# bme280_ssd1306.net
KiCad netlist of a schematic drawn in EAGLE
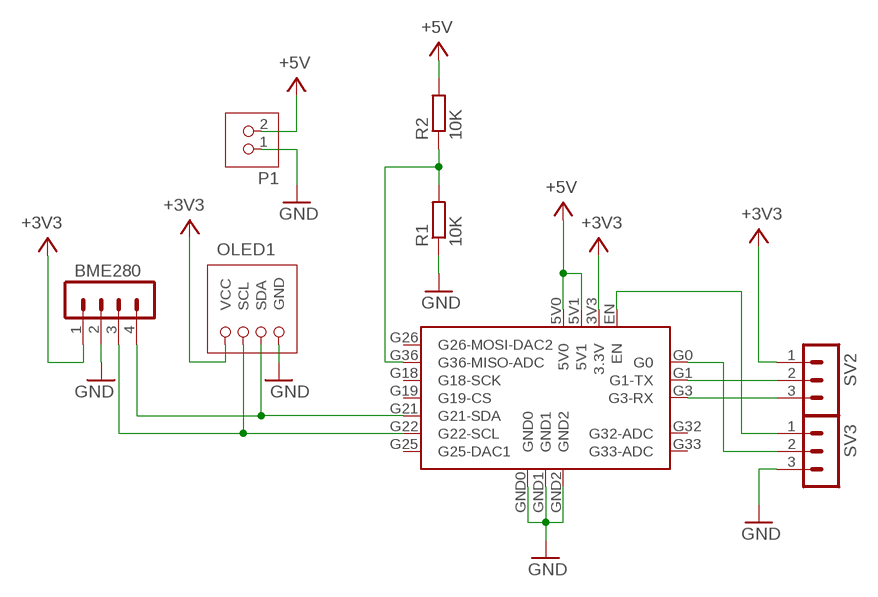
[diagram p0: schematic, sheet 1]

(export (version "E")
  (design (tool "Eeschema 10.0.6"))
  (components
    (comp (ref "BME280")
      (value "PINHEAD-MA04-1")
      (footprint "eagle-import:PINHEAD-MA04-1")
      (libsource (lib "eagle-import") (part "PINHEAD-MA04-1"))
    )
    (comp (ref "M5PICO1")
      (value "M5STAMP-PICO-SMD")
      (footprint "eagle-import:M5STAMP-PICO-SMD")
      (libsource (lib "eagle-import") (part "M5STAMP-PICO-SMD"))
    )
    (comp (ref "OLED1")
      (value "OLED-SSD1306-0.96")
      (footprint "eagle-import:OLED-I2C-0.96")
      (libsource (lib "eagle-import") (part "OLED-SSD1306-0.96"))
    )
    (comp (ref "P1")
      (value "JST-PH2")
      (footprint "eagle-import:JST-PH2")
      (libsource (lib "eagle-import") (part "JST-PH2"))
    )
    (comp (ref "R1")
      (value "10K")
      (footprint "eagle-import:R3216")
      (libsource (lib "eagle-import") (part "R-EU_R3216"))
    )
    (comp (ref "R2")
      (value "10K")
      (footprint "eagle-import:R3216")
      (libsource (lib "eagle-import") (part "R-EU_R3216"))
    )
    (comp (ref "SV2")
      (value "PINHEAD-MA03-1")
      (footprint "eagle-import:PINHEAD-MA03-1")
      (libsource (lib "eagle-import") (part "PINHEAD-MA03-1"))
    )
    (comp (ref "SV3")
      (value "PINHEAD-MA03-1")
      (footprint "eagle-import:PINHEAD-MA03-1")
      (libsource (lib "eagle-import") (part "PINHEAD-MA03-1"))
    )
  )
  (nets
    (net (code "1") (name "+3V3") (class "Default")
      (node (ref "BME280") (pin "1") (pinfunction "1_1") (pintype "passive"))
      (node (ref "M5PICO1") (pin "3V3") (pinfunction "3.3V_3V3") (pintype "bidirectional"))
      (node (ref "OLED1") (pin "VCC") (pinfunction "VCC_VCC") (pintype "bidirectional"))
      (node (ref "SV2") (pin "1") (pinfunction "1_1") (pintype "passive"))
    )
    (net (code "2") (name "+5V") (class "Default")
      (node (ref "M5PICO1") (pin "5V0") (pinfunction "5V0_5V0") (pintype "bidirectional"))
      (node (ref "M5PICO1") (pin "5V1") (pinfunction "5V1_5V1") (pintype "bidirectional"))
      (node (ref "P1") (pin "2") (pinfunction "2_2") (pintype "passive"))
      (node (ref "R2") (pin "2") (pinfunction "2_2") (pintype "passive"))
    )
    (net (code "3") (name "GND") (class "Default")
      (node (ref "BME280") (pin "2") (pinfunction "2_2") (pintype "passive"))
      (node (ref "M5PICO1") (pin "GND0") (pinfunction "GND0_GND0") (pintype "bidirectional"))
      (node (ref "M5PICO1") (pin "GND1") (pinfunction "GND1_GND1") (pintype "bidirectional"))
      (node (ref "M5PICO1") (pin "GND2") (pinfunction "GND2_GND2") (pintype "bidirectional"))
      (node (ref "OLED1") (pin "GND") (pinfunction "GND_GND") (pintype "bidirectional"))
      (node (ref "P1") (pin "1") (pinfunction "1_1") (pintype "passive"))
      (node (ref "R1") (pin "1") (pinfunction "1_1") (pintype "passive"))
      (node (ref "SV3") (pin "3") (pinfunction "3_3") (pintype "passive"))
    )
    (net (code "4") (name "Net-(M5PICO1-G1-TX)") (class "Default")
      (node (ref "M5PICO1") (pin "G1") (pinfunction "G1-TX_G1") (pintype "bidirectional"))
      (node (ref "SV2") (pin "2") (pinfunction "2_2") (pintype "passive"))
    )
    (net (code "5") (name "Net-(M5PICO1-G3-RX)") (class "Default")
      (node (ref "M5PICO1") (pin "G3") (pinfunction "G3-RX_G3") (pintype "bidirectional"))
      (node (ref "SV2") (pin "3") (pinfunction "3_3") (pintype "passive"))
    )
    (net (code "6") (name "Net-(M5PICO1-G21-SDA)") (class "Default")
      (node (ref "BME280") (pin "4") (pinfunction "4_4") (pintype "passive"))
      (node (ref "M5PICO1") (pin "G21") (pinfunction "G21-SDA_G21") (pintype "bidirectional"))
      (node (ref "OLED1") (pin "SDA") (pinfunction "SDA_SDA") (pintype "bidirectional"))
    )
    (net (code "7") (name "Net-(M5PICO1-G22-SCL)") (class "Default")
      (node (ref "BME280") (pin "3") (pinfunction "3_3") (pintype "passive"))
      (node (ref "M5PICO1") (pin "G22") (pinfunction "G22-SCL_G22") (pintype "bidirectional"))
      (node (ref "OLED1") (pin "SCL") (pinfunction "SCL_SCL") (pintype "bidirectional"))
    )
    (net (code "8") (name "Net-(M5PICO1-G36-MISO-ADC)") (class "Default")
      (node (ref "M5PICO1") (pin "G36") (pinfunction "G36-MISO-ADC_G36") (pintype "bidirectional"))
      (node (ref "R1") (pin "2") (pinfunction "2_2") (pintype "passive"))
      (node (ref "R2") (pin "1") (pinfunction "1_1") (pintype "passive"))
    )
    (net (code "9") (name "Net-(M5PICO1-PadEN)") (class "Default")
      (node (ref "M5PICO1") (pin "EN") (pinfunction "EN_EN") (pintype "bidirectional"))
      (node (ref "SV3") (pin "1") (pinfunction "1_1") (pintype "passive"))
    )
    (net (code "10") (name "Net-(M5PICO1-PadG0)") (class "Default")
      (node (ref "M5PICO1") (pin "G0") (pinfunction "G0_G0") (pintype "bidirectional"))
      (node (ref "SV3") (pin "2") (pinfunction "2_2") (pintype "passive"))
    )
    (net (code "11") (name "unconnected-(M5PICO1-G18-SCK-PadG18)") (class "Default")
      (node (ref "M5PICO1") (pin "G18") (pinfunction "G18-SCK_G18") (pintype "bidirectional"))
    )
    (net (code "12") (name "unconnected-(M5PICO1-G19-CS-PadG19)") (class "Default")
      (node (ref "M5PICO1") (pin "G19") (pinfunction "G19-CS_G19") (pintype "bidirectional"))
    )
    (net (code "13") (name "unconnected-(M5PICO1-G25-DAC1-PadG25)") (class "Default")
      (node (ref "M5PICO1") (pin "G25") (pinfunction "G25-DAC1_G25") (pintype "bidirectional"))
    )
    (net (code "14") (name "unconnected-(M5PICO1-G26-MOSI-DAC2-PadG26)") (class "Default")
      (node (ref "M5PICO1") (pin "G26") (pinfunction "G26-MOSI-DAC2_G26") (pintype "bidirectional"))
    )
    (net (code "15") (name "unconnected-(M5PICO1-G32-ADC-PadG32)") (class "Default")
      (node (ref "M5PICO1") (pin "G32") (pinfunction "G32-ADC_G32") (pintype "bidirectional"))
    )
    (net (code "16") (name "unconnected-(M5PICO1-G33-ADC-PadG33)") (class "Default")
      (node (ref "M5PICO1") (pin "G33") (pinfunction "G33-ADC_G33") (pintype "bidirectional"))
    )
  )
)
